# Power_and_USB.net
KiCad netlist of a schematic drawn in Altium Designer
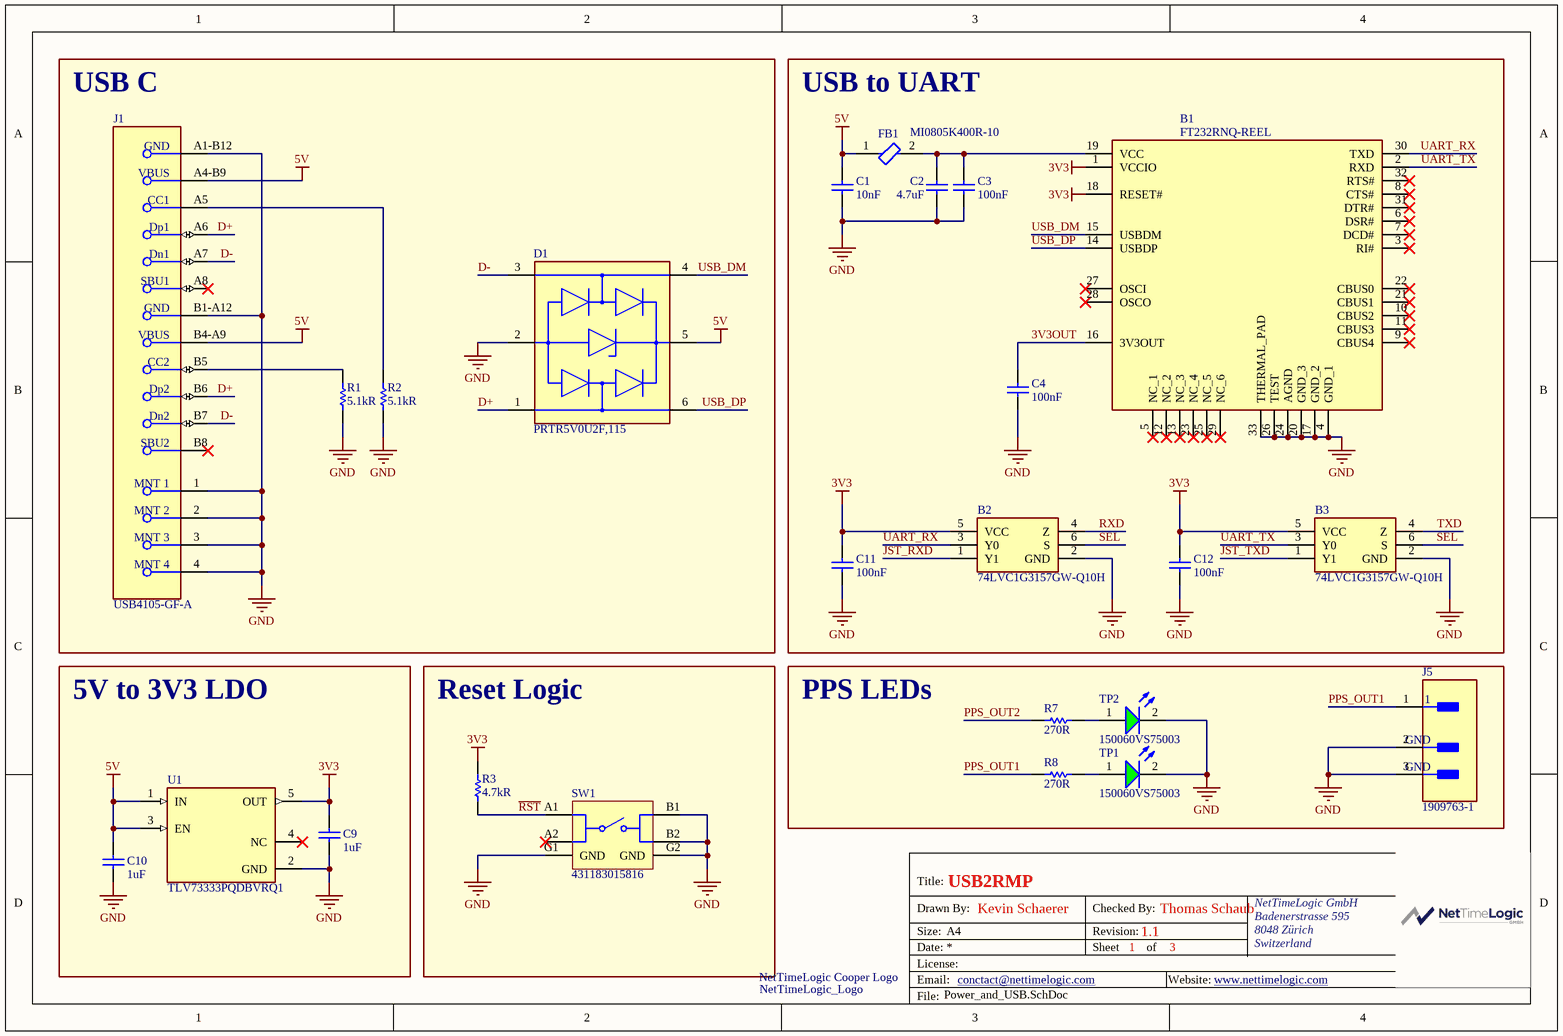
[diagram p0: Power_and_USB.SchDoc]

(export (version "E")
  (design (tool "Eeschema 10.0.6"))
  (components
    (comp (ref "1")
      (value "NetTimeLogic_Logo")
      (footprint "NetTimeLogic_Logo_25mm")
      (description "NetTimeLogic Cooper Logos 15mm,  25mm, 35mm, 50 mm")
      (libsource (lib "NetTimeLogic GmbH") (part "NetTimeLogic Cooper"))
    )
    (comp (ref "B1")
      (value "FT232RNQ-REEL")
      (footprint "QFN50P500X500X90-33N-D")
      (description "UART Interface IC USB Full Speed to Serial UART IC, Includes Oscillator and EEPROM, QFN-32")
      (fields (field (name "MOUSER PART NUMBER") "895-FT232RNQ-REEL"))
      (libsource (lib "NetTimeLogic GmbH") (part "FT232RNQ-REEL"))
    )
    (comp (ref "B2")
      (value "74LVC1G3157GW-Q10H")
      (footprint "SOT65P210X110-6N")
      (description "74LVC1G3157-Q100 - 2-channel analog multiplexer/demultiplexer@en-us")
      (fields (field (name "MOUSER PART NUMBER") "771-74LVC1G3157GWQ10"))
      (libsource (lib "NetTimeLogic GmbH") (part "74LVC1G3157GW-Q10H"))
    )
    (comp (ref "B3")
      (value "74LVC1G3157GW-Q10H")
      (footprint "SOT65P210X110-6N")
      (description "74LVC1G3157-Q100 - 2-channel analog multiplexer/demultiplexer@en-us")
      (fields (field (name "MOUSER PART NUMBER") "771-74LVC1G3157GWQ10"))
      (libsource (lib "NetTimeLogic GmbH") (part "74LVC1G3157GW-Q10H"))
    )
    (comp (ref "C1")
      (value "10nF")
      (footprint "FP-C0603C-CF-MFG")
      (description "CAP CER 10000PF 50V X7R 0603")
      (fields (field (name "TOLERANCE") "10%") (field (name "VOLTAGE") "50V"))
      (libsource (lib "NetTimeLogic GmbH") (part "CAP"))
    )
    (comp (ref "C2")
      (value "4.7uF")
      (footprint "CAPC1608X90X35LL15T15")
      (description "Cap Ceramic 4.7uF 6.3V X5R 20% SMD 0603 85C Paper T/R")
      (fields (field (name "TOLERANCE") "20%") (field (name "Comment") "C0603C475M9PACTU"))
      (libsource (lib "NetTimeLogic GmbH") (part "CAP"))
    )
    (comp (ref "C3")
      (value "100nF")
      (footprint "FP-C0603C-CF-MFG")
      (description "Cap Ceramic 0.1uF 16V X7R 10% SMD 0603 125°C Paper T/R")
      (fields (field (name "VOLTAGE") "16V") (field (name "TOLERANCE") "10%"))
      (libsource (lib "NetTimeLogic GmbH") (part "C0402C104K8PACTU"))
    )
    (comp (ref "C4")
      (value "100nF")
      (footprint "FP-C0603C-CF-MFG")
      (description "Cap Ceramic 0.1uF 16V X7R 10% SMD 0603 125°C Paper T/R")
      (fields (field (name "VOLTAGE") "16V") (field (name "TOLERANCE") "10%"))
      (libsource (lib "NetTimeLogic GmbH") (part "C0402C104K8PACTU"))
    )
    (comp (ref "C9")
      (value "1uF")
      (footprint "CAPC1608X90X35LL15T15")
      (description "Cap Ceramic 1uF 16V X7R 10% SMD 0603 125°C Paper T/R")
      (fields (field (name "TOLERANCE") "10%") (field (name "VOLTAGE") "16V"))
      (libsource (lib "NetTimeLogic GmbH") (part "CAP"))
    )
    (comp (ref "C10")
      (value "1uF")
      (footprint "CAPC1608X90X35LL15T15")
      (description "Cap Ceramic 1uF 16V X7R 10% SMD 0603 125°C Paper T/R")
      (fields (field (name "TOLERANCE") "10%") (field (name "VOLTAGE") "16V"))
      (libsource (lib "NetTimeLogic GmbH") (part "CAP"))
    )
    (comp (ref "C11")
      (value "100nF")
      (footprint "FP-C0603C-CF-MFG")
      (description "Cap Ceramic 0.1uF 16V X7R 10% SMD 0603 125°C Paper T/R")
      (fields (field (name "VOLTAGE") "16V") (field (name "TOLERANCE") "10%"))
      (libsource (lib "NetTimeLogic GmbH") (part "C0402C104K8PACTU"))
    )
    (comp (ref "C12")
      (value "100nF")
      (footprint "FP-C0603C-CF-MFG")
      (description "Cap Ceramic 0.1uF 16V X7R 10% SMD 0603 125°C Paper T/R")
      (fields (field (name "VOLTAGE") "16V") (field (name "TOLERANCE") "10%"))
      (libsource (lib "NetTimeLogic GmbH") (part "C0402C104K8PACTU"))
    )
    (comp (ref "D1")
      (value "PRTR5V0U2F,115")
      (footprint "FP-SOT886-MFG")
      (description "TVS DIODE 5.5VWM SOT886")
      (libsource (lib "NetTimeLogic GmbH") (part "703b586617e7d68525a27545bfdaf8c"))
    )
    (comp (ref "FB1")
      (value "MI0805K400R-10")
      (footprint "FP-MI0805-MFG")
      (description "Ferrite Chip, 1 Function(s), 1.5A, 2 Pin(s)")
      (libsource (lib "NetTimeLogic GmbH") (part "5f30dd21d616792df468990f7003faa"))
    )
    (comp (ref "J1")
      (value "USB4105-GF-A")
      (footprint "FP-USB4105-GF-A-MFG")
      (description "Conn USB 2.0 Type C RCP 24 POS 0.3mm/0.5mm Solder RA SMD 24 Terminal 1 Port T/R")
      (libsource (lib "NetTimeLogic GmbH") (part "e7c17a616881a82b79941196b4bec10"))
    )
    (comp (ref "J5")
      (value "1909763-1")
      (footprint "FP-1909763-1-MFG")
      (description "RF COAX Connector, UMCC PLUG, 50 OHM, PCB; Co; Connector Type: UMCC Coaxial; Body Style: Straight")
      (libsource (lib "NetTimeLogic GmbH") (part "569be1477c50da64a8977defc59cdd7"))
    )
    (comp (ref "R1")
      (value "5.1kR")
      (footprint "RESC1608X55X25LL10T15")
      (description "SMD Chip Resistor, 5.1 kOhm, ± 1%, 100 mW, 0603 [1608 Metric], Thick Film, General Purpose")
      (fields (field (name "TOLERANCE") "1%") (field (name "Comment") "RC0603FR-075K1L"))
      (libsource (lib "NetTimeLogic GmbH") (part "RES-2"))
    )
    (comp (ref "R2")
      (value "5.1kR")
      (footprint "RESC1608X55X25LL10T15")
      (description "SMD Chip Resistor, 5.1 kOhm, ± 1%, 100 mW, 0603 [1608 Metric], Thick Film, General Purpose")
      (fields (field (name "TOLERANCE") "1%") (field (name "Comment") "RC0603FR-075K1L"))
      (libsource (lib "NetTimeLogic GmbH") (part "RES-2"))
    )
    (comp (ref "R3")
      (value "4.7kR")
      (footprint "RESC1608X55X25LL10T15")
      (description "Res Thick Film 0603 4.7K Ohm 1% 1/10W ±100ppm/°C Molded SMD Paper T/R")
      (fields (field (name "TOLERANCE") "1%") (field (name "Comment") "RC0603FR-074K7L"))
      (libsource (lib "NetTimeLogic GmbH") (part "RES-2"))
    )
    (comp (ref "R7")
      (value "270R")
      (footprint "RESC1608X55X25LL10T15")
      (description "SMD Chip Resistor, 270 Ohm, ± 1%, 100 mW, 0603 [1608 Metric], Thick Film, General Purpose")
      (fields (field (name "TOLERANCE") "1%") (field (name "Comment") "RC0603FR-07270RL"))
      (libsource (lib "NetTimeLogic GmbH") (part "RES-2"))
    )
    (comp (ref "R8")
      (value "270R")
      (footprint "RESC1608X55X25LL10T15")
      (description "SMD Chip Resistor, 270 Ohm, ± 1%, 100 mW, 0603 [1608 Metric], Thick Film, General Purpose")
      (fields (field (name "TOLERANCE") "1%") (field (name "Comment") "RC0603FR-07270RL"))
      (libsource (lib "NetTimeLogic GmbH") (part "RES-2"))
    )
    (comp (ref "SW1")
      (value "431183015816")
      (footprint "WS-TASV_L5W5H1.5_4311x30158x6")
      (description "Switch Tactile Spst-no 0.02A 15V")
      (libsource (lib "NetTimeLogic GmbH") (part "SPST-NO_4P_2GND"))
    )
    (comp (ref "TP1")
      (value "150060VS75003")
      (footprint "WL-SMCW_0603_150060xx75003")
      (description "Led, Bright Green, 100Mcd, 572Nm Rohs Compliant: Yes")
      (libsource (lib "NetTimeLogic GmbH") (part "LED_Green_1A-2K"))
    )
    (comp (ref "TP2")
      (value "150060VS75003")
      (footprint "WL-SMCW_0603_150060xx75003")
      (description "Led, Bright Green, 100Mcd, 572Nm Rohs Compliant: Yes")
      (libsource (lib "NetTimeLogic GmbH") (part "LED_Green_1A-2K"))
    )
    (comp (ref "U1")
      (value "TLV73333PQDBVRQ1")
      (footprint "FP-DBV0005A-MFG")
      (description "Automotive 300-mA, low-IQ, low-dropout voltage regulator with enable 5-SOT-23 -40 to 125")
      (libsource (lib "NetTimeLogic GmbH") (part "9fe5a7569a672cc344d83ad3dd2d204"))
    )
  )
  (nets
    (net (code "1") (name "/3V3OUT") (class "Default")
      (node (ref "B1") (pin "16") (pinfunction "3V3OUT_16") (pintype "passive"))
      (node (ref "C4") (pin "2") (pinfunction "2_2") (pintype "passive"))
    )
    (net (code "2") (name "/D+") (class "Default")
      (node (ref "D1") (pin "1") (pinfunction "I/O1_1") (pintype "passive"))
      (node (ref "J1") (pin "A6") (pinfunction "Dp1_A6") (pintype "bidirectional"))
      (node (ref "J1") (pin "B6") (pinfunction "Dp2_B6") (pintype "bidirectional"))
    )
    (net (code "3") (name "/D-") (class "Default")
      (node (ref "D1") (pin "3") (pinfunction "I/O2_3") (pintype "passive"))
      (node (ref "J1") (pin "A7") (pinfunction "Dn1_A7") (pintype "bidirectional"))
      (node (ref "J1") (pin "B7") (pinfunction "Dn2_B7") (pintype "bidirectional"))
    )
    (net (code "4") (name "/JST_RXD") (class "Default")
      (node (ref "B2") (pin "1") (pinfunction "Y1_1") (pintype "passive"))
    )
    (net (code "5") (name "/JST_TXD") (class "Default")
      (node (ref "B3") (pin "1") (pinfunction "Y1_1") (pintype "passive"))
    )
    (net (code "6") (name "/PPS_OUT1") (class "Default")
      (node (ref "J5") (pin "1") (pinfunction "1_1") (pintype "passive"))
      (node (ref "R8") (pin "1") (pinfunction "1_1") (pintype "passive"))
    )
    (net (code "7") (name "/PPS_OUT2") (class "Default")
      (node (ref "R7") (pin "1") (pinfunction "1_1") (pintype "passive"))
    )
    (net (code "8") (name "/RXD") (class "Default")
      (node (ref "B2") (pin "4") (pinfunction "Z_4") (pintype "passive"))
    )
    (net (code "9") (name "/SEL") (class "Default")
      (node (ref "B2") (pin "6") (pinfunction "S_6") (pintype "passive"))
      (node (ref "B3") (pin "6") (pinfunction "S_6") (pintype "passive"))
    )
    (net (code "10") (name "/TXD") (class "Default")
      (node (ref "B3") (pin "4") (pinfunction "Z_4") (pintype "passive"))
    )
    (net (code "11") (name "/UART_RX") (class "Default")
      (node (ref "B1") (pin "30") (pinfunction "TXD_30") (pintype "passive"))
      (node (ref "B2") (pin "3") (pinfunction "Y0_3") (pintype "passive"))
    )
    (net (code "12") (name "/UART_TX") (class "Default")
      (node (ref "B1") (pin "2") (pinfunction "RXD_2") (pintype "passive"))
      (node (ref "B3") (pin "3") (pinfunction "Y0_3") (pintype "passive"))
    )
    (net (code "13") (name "/USB_DM") (class "Default")
      (node (ref "B1") (pin "15") (pinfunction "USBDM_15") (pintype "passive"))
      (node (ref "D1") (pin "4") (pinfunction "I/O2_4") (pintype "passive"))
    )
    (net (code "14") (name "/USB_DP") (class "Default")
      (node (ref "B1") (pin "14") (pinfunction "USBDP_14") (pintype "passive"))
      (node (ref "D1") (pin "6") (pinfunction "I/O1_6") (pintype "passive"))
    )
    (net (code "15") (name "/~{RST}") (class "Default")
      (node (ref "R3") (pin "2") (pinfunction "2_2") (pintype "passive"))
      (node (ref "SW1") (pin "A1") (pinfunction "A1_A1") (pintype "passive"))
    )
    (net (code "16") (name "3V3") (class "Default")
      (node (ref "B1") (pin "1") (pinfunction "VCCIO_1") (pintype "passive"))
      (node (ref "B1") (pin "18") (pinfunction "RESET#_18") (pintype "passive"))
      (node (ref "B2") (pin "5") (pinfunction "VCC_5") (pintype "passive"))
      (node (ref "B3") (pin "5") (pinfunction "VCC_5") (pintype "passive"))
      (node (ref "C11") (pin "2") (pinfunction "2_2") (pintype "passive"))
      (node (ref "C12") (pin "2") (pinfunction "2_2") (pintype "passive"))
      (node (ref "C9") (pin "2") (pinfunction "2_2") (pintype "passive"))
      (node (ref "R3") (pin "1") (pinfunction "1_1") (pintype "passive"))
      (node (ref "U1") (pin "5") (pinfunction "OUT_5") (pintype "output"))
    )
    (net (code "17") (name "5V") (class "Default")
      (node (ref "C1") (pin "2") (pinfunction "2_2") (pintype "passive"))
      (node (ref "C10") (pin "2") (pinfunction "2_2") (pintype "passive"))
      (node (ref "D1") (pin "5") (pinfunction "VCC_5") (pintype "power_in"))
      (node (ref "FB1") (pin "1") (pinfunction "1_1") (pintype "passive"))
      (node (ref "J1") (pin "A4-B9") (pinfunction "VBUS_A4-B9") (pintype "power_in"))
      (node (ref "J1") (pin "B4-A9") (pinfunction "VBUS_B4-A9") (pintype "power_in"))
      (node (ref "U1") (pin "1") (pinfunction "IN_1") (pintype "input"))
      (node (ref "U1") (pin "3") (pinfunction "EN_3") (pintype "input"))
    )
    (net (code "18") (name "GND") (class "Default")
      (node (ref "B1") (pin "17") (pinfunction "GND_2_17") (pintype "passive"))
      (node (ref "B1") (pin "20") (pinfunction "GND_3_20") (pintype "passive"))
      (node (ref "B1") (pin "24") (pinfunction "AGND_24") (pintype "passive"))
      (node (ref "B1") (pin "26") (pinfunction "TEST_26") (pintype "passive"))
      (node (ref "B1") (pin "33") (pinfunction "THERMAL_PAD_33") (pintype "passive"))
      (node (ref "B1") (pin "4") (pinfunction "GND_1_4") (pintype "passive"))
      (node (ref "B2") (pin "2") (pinfunction "GND_2") (pintype "passive"))
      (node (ref "B3") (pin "2") (pinfunction "GND_2") (pintype "passive"))
      (node (ref "C1") (pin "1") (pinfunction "1_1") (pintype "passive"))
      (node (ref "C10") (pin "1") (pinfunction "1_1") (pintype "passive"))
      (node (ref "C11") (pin "1") (pinfunction "1_1") (pintype "passive"))
      (node (ref "C12") (pin "1") (pinfunction "1_1") (pintype "passive"))
      (node (ref "C2") (pin "1") (pinfunction "1_1") (pintype "passive"))
      (node (ref "C3") (pin "1") (pinfunction "1_1") (pintype "passive"))
      (node (ref "C4") (pin "1") (pinfunction "1_1") (pintype "passive"))
      (node (ref "C9") (pin "1") (pinfunction "1_1") (pintype "passive"))
      (node (ref "D1") (pin "2") (pinfunction "GND_2") (pintype "power_in"))
      (node (ref "J1") (pin "1") (pinfunction "MNT_1_1") (pintype "power_in"))
      (node (ref "J1") (pin "2") (pinfunction "MNT_2_2") (pintype "power_in"))
      (node (ref "J1") (pin "3") (pinfunction "MNT_3_3") (pintype "power_in"))
      (node (ref "J1") (pin "4") (pinfunction "MNT_4_4") (pintype "power_in"))
      (node (ref "J1") (pin "A1-B12") (pinfunction "GND_A1-B12") (pintype "power_in"))
      (node (ref "J1") (pin "B1-A12") (pinfunction "GND_B1-A12") (pintype "power_in"))
      (node (ref "J5") (pin "2") (pinfunction "GND_2") (pintype "passive"))
      (node (ref "J5") (pin "3") (pinfunction "GND_3") (pintype "passive"))
      (node (ref "R1") (pin "1") (pinfunction "1_1") (pintype "passive"))
      (node (ref "R2") (pin "1") (pinfunction "1_1") (pintype "passive"))
      (node (ref "SW1") (pin "B1") (pinfunction "B1_B1") (pintype "passive"))
      (node (ref "SW1") (pin "B2") (pinfunction "B2_B2") (pintype "passive"))
      (node (ref "SW1") (pin "G1") (pinfunction "GND_G1") (pintype "passive"))
      (node (ref "SW1") (pin "G2") (pinfunction "GND_G2") (pintype "passive"))
      (node (ref "TP1") (pin "2") (pinfunction "K_2") (pintype "passive"))
      (node (ref "TP2") (pin "2") (pinfunction "K_2") (pintype "passive"))
      (node (ref "U1") (pin "2") (pinfunction "GND_2") (pintype "power_in"))
    )
    (net (code "19") (name "Net-(B1-VCC)") (class "Default")
      (node (ref "B1") (pin "19") (pinfunction "VCC_19") (pintype "passive"))
      (node (ref "C2") (pin "2") (pinfunction "2_2") (pintype "passive"))
      (node (ref "C3") (pin "2") (pinfunction "2_2") (pintype "passive"))
      (node (ref "FB1") (pin "2") (pinfunction "2_2") (pintype "passive"))
    )
    (net (code "20") (name "Net-(J1-CC1)") (class "Default")
      (node (ref "J1") (pin "A5") (pinfunction "CC1_A5") (pintype "power_in"))
      (node (ref "R2") (pin "2") (pinfunction "2_2") (pintype "passive"))
    )
    (net (code "21") (name "Net-(J1-CC2)") (class "Default")
      (node (ref "J1") (pin "B5") (pinfunction "CC2_B5") (pintype "bidirectional"))
      (node (ref "R1") (pin "2") (pinfunction "2_2") (pintype "passive"))
    )
    (net (code "22") (name "Net-(TP1-A)") (class "Default")
      (node (ref "R8") (pin "2") (pinfunction "2_2") (pintype "passive"))
      (node (ref "TP1") (pin "1") (pinfunction "A_1") (pintype "passive"))
    )
    (net (code "23") (name "Net-(TP2-A)") (class "Default")
      (node (ref "R7") (pin "2") (pinfunction "2_2") (pintype "passive"))
      (node (ref "TP2") (pin "1") (pinfunction "A_1") (pintype "passive"))
    )
    (net (code "24") (name "unconnected-(B1-CBUS0-Pad22)") (class "Default")
      (node (ref "B1") (pin "22") (pinfunction "CBUS0_22") (pintype "passive+no_connect"))
    )
    (net (code "25") (name "unconnected-(B1-CBUS1-Pad21)") (class "Default")
      (node (ref "B1") (pin "21") (pinfunction "CBUS1_21") (pintype "passive+no_connect"))
    )
    (net (code "26") (name "unconnected-(B1-CBUS2-Pad10)") (class "Default")
      (node (ref "B1") (pin "10") (pinfunction "CBUS2_10") (pintype "passive+no_connect"))
    )
    (net (code "27") (name "unconnected-(B1-CBUS3-Pad11)") (class "Default")
      (node (ref "B1") (pin "11") (pinfunction "CBUS3_11") (pintype "passive+no_connect"))
    )
    (net (code "28") (name "unconnected-(B1-CBUS4-Pad9)") (class "Default")
      (node (ref "B1") (pin "9") (pinfunction "CBUS4_9") (pintype "passive+no_connect"))
    )
    (net (code "29") (name "unconnected-(B1-CTS#-Pad8)") (class "Default")
      (node (ref "B1") (pin "8") (pinfunction "CTS#_8") (pintype "passive+no_connect"))
    )
    (net (code "30") (name "unconnected-(B1-DCD#-Pad7)") (class "Default")
      (node (ref "B1") (pin "7") (pinfunction "DCD#_7") (pintype "passive+no_connect"))
    )
    (net (code "31") (name "unconnected-(B1-DSR#-Pad6)") (class "Default")
      (node (ref "B1") (pin "6") (pinfunction "DSR#_6") (pintype "passive+no_connect"))
    )
    (net (code "32") (name "unconnected-(B1-DTR#-Pad31)") (class "Default")
      (node (ref "B1") (pin "31") (pinfunction "DTR#_31") (pintype "passive+no_connect"))
    )
    (net (code "33") (name "unconnected-(B1-NC_1-Pad5)") (class "Default")
      (node (ref "B1") (pin "5") (pinfunction "NC_1_5") (pintype "passive+no_connect"))
    )
    (net (code "34") (name "unconnected-(B1-NC_2-Pad12)") (class "Default")
      (node (ref "B1") (pin "12") (pinfunction "NC_2_12") (pintype "passive+no_connect"))
    )
    (net (code "35") (name "unconnected-(B1-NC_3-Pad13)") (class "Default")
      (node (ref "B1") (pin "13") (pinfunction "NC_3_13") (pintype "passive+no_connect"))
    )
    (net (code "36") (name "unconnected-(B1-NC_4-Pad23)") (class "Default")
      (node (ref "B1") (pin "23") (pinfunction "NC_4_23") (pintype "passive+no_connect"))
    )
    (net (code "37") (name "unconnected-(B1-NC_5-Pad25)") (class "Default")
      (node (ref "B1") (pin "25") (pinfunction "NC_5_25") (pintype "passive+no_connect"))
    )
    (net (code "38") (name "unconnected-(B1-NC_6-Pad29)") (class "Default")
      (node (ref "B1") (pin "29") (pinfunction "NC_6_29") (pintype "passive+no_connect"))
    )
    (net (code "39") (name "unconnected-(B1-OSCI-Pad27)") (class "Default")
      (node (ref "B1") (pin "27") (pinfunction "OSCI_27") (pintype "passive+no_connect"))
    )
    (net (code "40") (name "unconnected-(B1-OSCO-Pad28)") (class "Default")
      (node (ref "B1") (pin "28") (pinfunction "OSCO_28") (pintype "passive+no_connect"))
    )
    (net (code "41") (name "unconnected-(B1-RI#-Pad3)") (class "Default")
      (node (ref "B1") (pin "3") (pinfunction "RI#_3") (pintype "passive+no_connect"))
    )
    (net (code "42") (name "unconnected-(B1-RTS#-Pad32)") (class "Default")
      (node (ref "B1") (pin "32") (pinfunction "RTS#_32") (pintype "passive+no_connect"))
    )
    (net (code "43") (name "unconnected-(J1-SBU1-PadA8)") (class "Default")
      (node (ref "J1") (pin "A8") (pinfunction "SBU1_A8") (pintype "bidirectional+no_connect"))
    )
    (net (code "44") (name "unconnected-(J1-SBU2-PadB8)") (class "Default")
      (node (ref "J1") (pin "B8") (pinfunction "SBU2_B8") (pintype "power_in+no_connect"))
    )
    (net (code "45") (name "unconnected-(SW1-PadA2)") (class "Default")
      (node (ref "SW1") (pin "A2") (pinfunction "A2_A2") (pintype "passive+no_connect"))
    )
    (net (code "46") (name "unconnected-(U1-NC-Pad4)") (class "Default")
      (node (ref "U1") (pin "4") (pinfunction "NC_4") (pintype "passive+no_connect"))
    )
  )
)
